# 2_DAC_ADC.net
KiCad netlist of a schematic drawn in Altium Designer
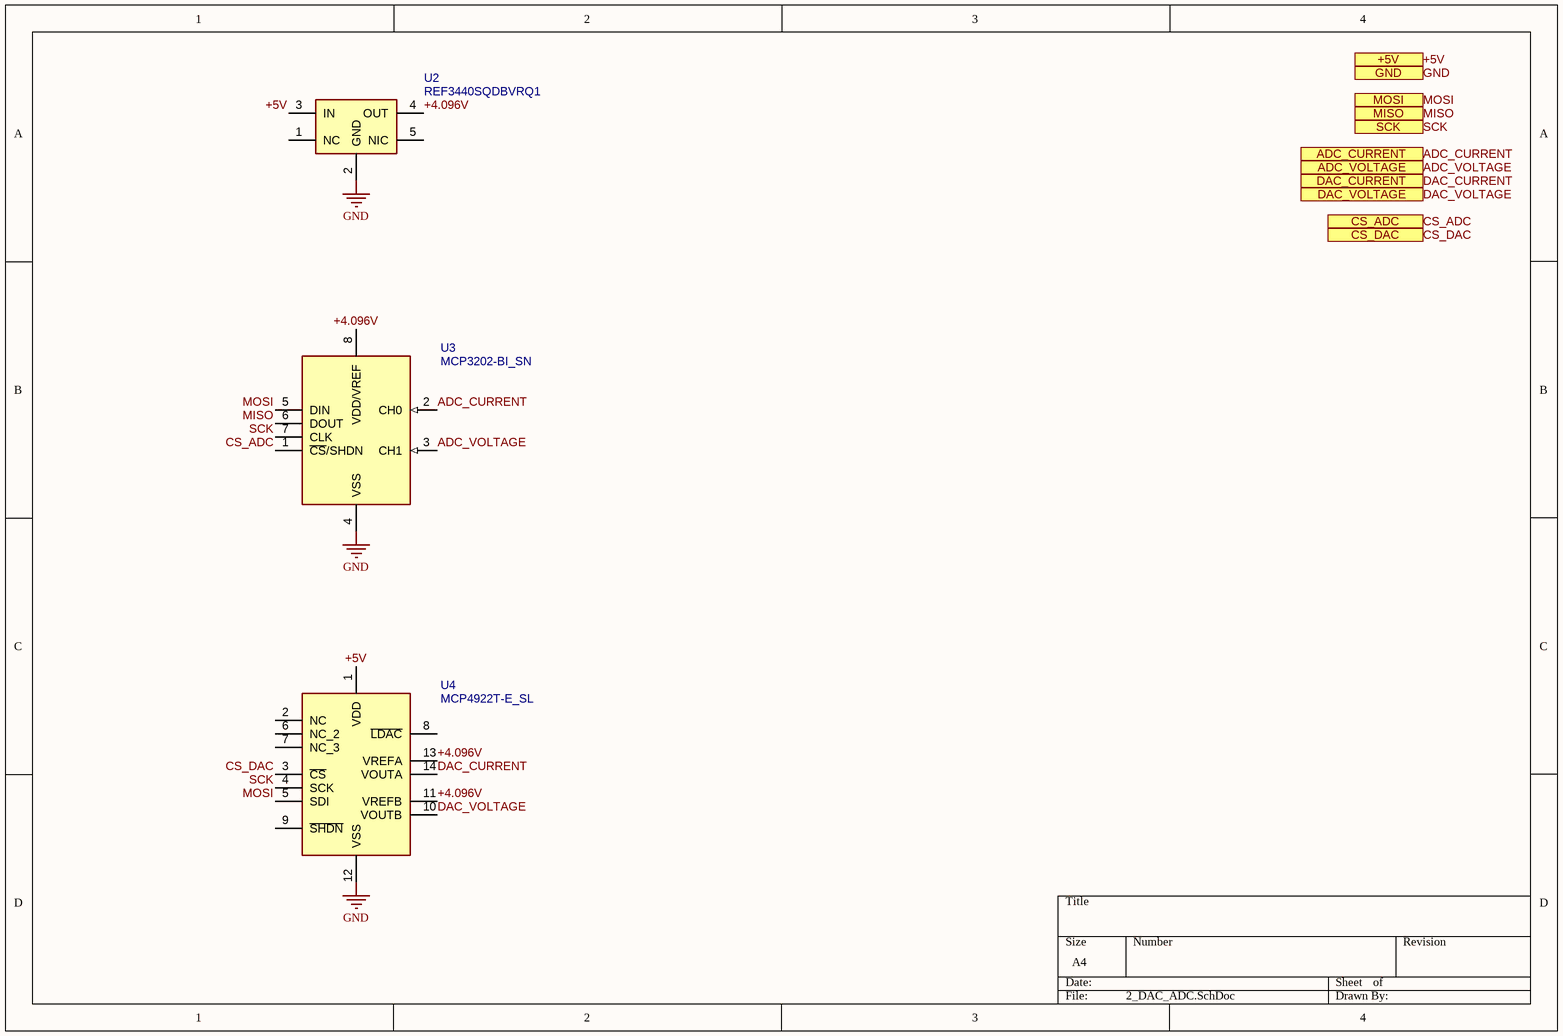
[diagram p0: 2_DAC_ADC.SchDoc]

(export (version "E")
  (design (tool "Eeschema 10.0.6"))
  (components
    (comp (ref "U2")
      (value "REF3440SQDBVRQ1")
      (footprint "SOT95P280X145-5N")
      (description "Integrated Circuit")
      (fields (field (name "MOUSER PART NUMBER") "595-REF3440SQDBVRQ1"))
      (libsource (lib "PowerSupplyPE") (part "REF3440SQDBVRQ1"))
    )
    (comp (ref "U3")
      (value "MCP3202-BI_SN")
      (footprint "SOIC127P600X175-8N")
      (description "Integrated Circuit")
      (fields
        (field (name "MANUFACTURER_PART_NUMBER") "MCP3202-BI/SN")
        (field (name "MOUSER PART NUMBER") "579-MCP3202BISN")
      )
      (libsource (lib "PowerSupplyPE") (part "MCP3202-BI_SN"))
    )
    (comp (ref "U4")
      (value "MCP4922T-E_SL")
      (footprint "SOIC127P600X175-14N")
      (description "Undefined or Miscellaneous")
      (fields
        (field (name "MANUFACTURER_PART_NUMBER") "MCP4922T-E/SL")
        (field (name "MOUSER PART NUMBER") "579-MCP4922T-E/SL")
      )
      (libsource (lib "PowerSupplyPE") (part "MCP4922T-E_SL"))
    )
  )
  (nets
    (net (code "1") (name "/+4.096V") (class "Default")
      (node (ref "U2") (pin "4") (pinfunction "OUT_4") (pintype "passive"))
      (node (ref "U3") (pin "8") (pinfunction "VDD/VREF_8") (pintype "power_in"))
      (node (ref "U4") (pin "11") (pinfunction "VREFB_11") (pintype "passive"))
      (node (ref "U4") (pin "13") (pinfunction "VREFA_13") (pintype "passive"))
    )
    (net (code "2") (name "/+5V") (class "Default")
      (node (ref "U2") (pin "3") (pinfunction "IN_3") (pintype "passive"))
      (node (ref "U4") (pin "1") (pinfunction "VDD_1") (pintype "power_in"))
    )
    (net (code "3") (name "/ADC_CURRENT") (class "Default")
      (node (ref "U3") (pin "2") (pinfunction "CH0_2") (pintype "input"))
    )
    (net (code "4") (name "/ADC_VOLTAGE") (class "Default")
      (node (ref "U3") (pin "3") (pinfunction "CH1_3") (pintype "input"))
    )
    (net (code "5") (name "/CS_ADC") (class "Default")
      (node (ref "U3") (pin "1") (pinfunction "~{CS}/SHDN_1") (pintype "passive"))
    )
    (net (code "6") (name "/CS_DAC") (class "Default")
      (node (ref "U4") (pin "3") (pinfunction "~{CS}_3") (pintype "passive"))
    )
    (net (code "7") (name "/DAC_CURRENT") (class "Default")
      (node (ref "U4") (pin "14") (pinfunction "VOUTA_14") (pintype "passive"))
    )
    (net (code "8") (name "/DAC_VOLTAGE") (class "Default")
      (node (ref "U4") (pin "10") (pinfunction "VOUTB_10") (pintype "passive"))
    )
    (net (code "9") (name "/MISO") (class "Default")
      (node (ref "U3") (pin "6") (pinfunction "DOUT_6") (pintype "passive"))
    )
    (net (code "10") (name "/MOSI") (class "Default")
      (node (ref "U3") (pin "5") (pinfunction "DIN_5") (pintype "passive"))
      (node (ref "U4") (pin "5") (pinfunction "SDI_5") (pintype "passive"))
    )
    (net (code "11") (name "/SCK") (class "Default")
      (node (ref "U3") (pin "7") (pinfunction "CLK_7") (pintype "passive"))
      (node (ref "U4") (pin "4") (pinfunction "SCK_4") (pintype "passive"))
    )
    (net (code "12") (name "GND") (class "Default")
      (node (ref "U2") (pin "2") (pinfunction "GND_2") (pintype "passive"))
      (node (ref "U3") (pin "4") (pinfunction "VSS_4") (pintype "power_in"))
      (node (ref "U4") (pin "12") (pinfunction "VSS_12") (pintype "passive"))
    )
    (net (code "13") (name "unconnected-(U2-NC-Pad1)") (class "Default")
      (node (ref "U2") (pin "1") (pinfunction "NC_1") (pintype "passive"))
    )
    (net (code "14") (name "unconnected-(U2-NIC-Pad5)") (class "Default")
      (node (ref "U2") (pin "5") (pinfunction "NIC_5") (pintype "passive"))
    )
    (net (code "15") (name "unconnected-(U4-NC-Pad2)") (class "Default")
      (node (ref "U4") (pin "2") (pinfunction "NC_2") (pintype "passive"))
    )
    (net (code "16") (name "unconnected-(U4-NC_2-Pad6)") (class "Default")
      (node (ref "U4") (pin "6") (pinfunction "NC_2_6") (pintype "passive"))
    )
    (net (code "17") (name "unconnected-(U4-NC_3-Pad7)") (class "Default")
      (node (ref "U4") (pin "7") (pinfunction "NC_3_7") (pintype "passive"))
    )
    (net (code "18") (name "unconnected-(U4-~{LDAC}-Pad8)") (class "Default")
      (node (ref "U4") (pin "8") (pinfunction "~{LDAC}_8") (pintype "passive"))
    )
    (net (code "19") (name "unconnected-(U4-~{SHDN}-Pad9)") (class "Default")
      (node (ref "U4") (pin "9") (pinfunction "~{SHDN}_9") (pintype "passive"))
    )
  )
)
